# B303AA.net
KiCad netlist of a schematic drawn in Altium Designer
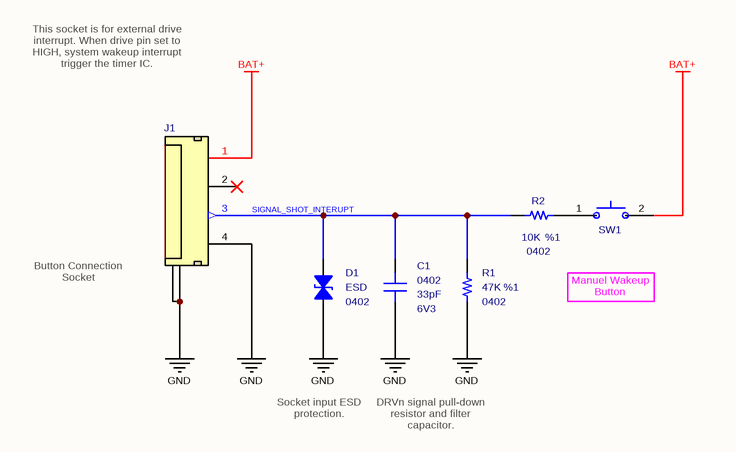
[diagram p0: B303AA.SchDoc]

(export (version "E")
  (design (tool "Eeschema 10.0.6"))
  (components
    (comp (ref "C1")
      (value "33pF")
      (footprint "CAPACITOR_0402")
      (description "Capacitor - 33pF [0402] (Ceramic)")
      (fields
        (field (name "MANUFACTURER_PART_NUMBER") "C0402C330J9RACAUTO")
        (field (name "MOUSER_PART_NUMBER") "80-C0402C330J9RAUTO")
        (field (name "CASE") "0402")
        (field (name "VOLTAGE") "6V3")
      )
      (libsource (lib "Ovoo_Schematic") (part "Capacitor - 33pF [0402-6V3]"))
    )
    (comp (ref "D1")
      (value "ESD Suppressors")
      (footprint "ESD_0402")
      (description "TVS Diode (Bi-directional)")
      (fields
        (field (name "MANUFACTURER_PART_NUMBER") "0402ESDA-MLP1")
        (field (name "MOUSER_PART_NUMBER") "504-0402ESDA-MLP1")
        (field (name "CASE") "0402")
      )
      (libsource (lib "Ovoo_Schematic") (part "Diode - ESD Protection"))
    )
    (comp (ref "J1")
      (value "Shot Button Socket")
      (footprint "Connector_Tunic 4P - H")
      (description "Mini Tunic Connector with 4P")
      (fields
        (field (name "MANUFACTURER_PART_NUMBER") "53261-0471")
        (field (name "MOUSER_PART_NUMBER") "538-53261-0471")
      )
      (libsource (lib "Ovoo_Schematic") (part "Connector - Mini Tunic 4P (1.25)"))
    )
    (comp (ref "R1")
      (value "47K")
      (footprint "RESISTOR_0402")
      (description "Thick Film Resistors - SMD 1/16 W 47 Kohms 1%")
      (fields
        (field (name "MANUFACTURER_PART_NUMBER") "CRCW040247K0FKED")
        (field (name "MOUSER_PART_NUMBER") "71-CRCW0402-47K-E3")
        (field (name "TOLERANCE") "%1")
        (field (name "CASE") "0402")
      )
      (libsource (lib "Ovoo_Schematic") (part "Resistor - 47K"))
    )
    (comp (ref "R2")
      (value "10K")
      (footprint "RESISTOR_0402")
      (description "Thick Film Resistors - SMD 1/16 W 10 Kohms 1%")
      (fields
        (field (name "MANUFACTURER_PART_NUMBER") "CRCW040210K0FKED")
        (field (name "MOUSER_PART_NUMBER") "71-CRCW0402-10K-E3")
        (field (name "TOLERANCE") "%1")
        (field (name "CASE") "0402")
      )
      (libsource (lib "Ovoo_Schematic") (part "Resistor - 10K"))
    )
    (comp (ref "SW1")
      (value "Tactile Switches")
      (footprint "PTS526_Switch")
      (description "Tactile Switches 50mA 12VDC, 5.2x5.2mm, 0.8mm H, 260gf, G leads.")
      (fields
        (field (name "MANUFACTURER_PART_NUMBER") "PTS526 SK08 SMTR2 LFS")
        (field (name "MOUSER_PART_NUMBER") "611-PTS526SK08SMTR2L")
      )
      (libsource (lib "Ovoo_Library") (part "Switch - Tactile (SMD)"))
    )
  )
  (nets
    (net (code "1") (name "/SIGNAL_SHOT_INTERUPT") (class "Default")
      (node (ref "C1") (pin "2") (pinfunction "2_2") (pintype "passive"))
      (node (ref "D1") (pin "2") (pinfunction "2_2") (pintype "passive"))
      (node (ref "J1") (pin "3") (pinfunction "Button_3") (pintype "output"))
      (node (ref "R1") (pin "2") (pinfunction "2_2") (pintype "passive"))
      (node (ref "R2") (pin "2") (pinfunction "2_2") (pintype "passive"))
    )
    (net (code "2") (name "BAT+") (class "Default")
      (node (ref "J1") (pin "1") (pinfunction "BAT+_1") (pintype "power_in"))
      (node (ref "SW1") (pin "2") (pinfunction "COM_2") (pintype "passive"))
    )
    (net (code "3") (name "GND") (class "Default")
      (node (ref "C1") (pin "1") (pinfunction "1_1") (pintype "passive"))
      (node (ref "D1") (pin "1") (pinfunction "1_1") (pintype "passive"))
      (node (ref "J1") (pin "4") (pinfunction "GND_4") (pintype "power_in"))
      (node (ref "J1") (pin "5") (pinfunction "Termination_5") (pintype "passive"))
      (node (ref "J1") (pin "6") (pinfunction "Termination_6") (pintype "passive"))
      (node (ref "R1") (pin "1") (pinfunction "1_1") (pintype "passive"))
    )
    (net (code "4") (name "Net-(SW1-NC)") (class "Default")
      (node (ref "R2") (pin "1") (pinfunction "1_1") (pintype "passive"))
      (node (ref "SW1") (pin "1") (pinfunction "NC_1") (pintype "passive"))
    )
    (net (code "5") (name "unconnected-(J1-NC-Pad2)") (class "Default")
      (node (ref "J1") (pin "2") (pinfunction "NC_2") (pintype "passive+no_connect"))
    )
  )
)
